# STRWHL-S05-V00-Screen.net
KiCad netlist of a schematic drawn in Altium Designer
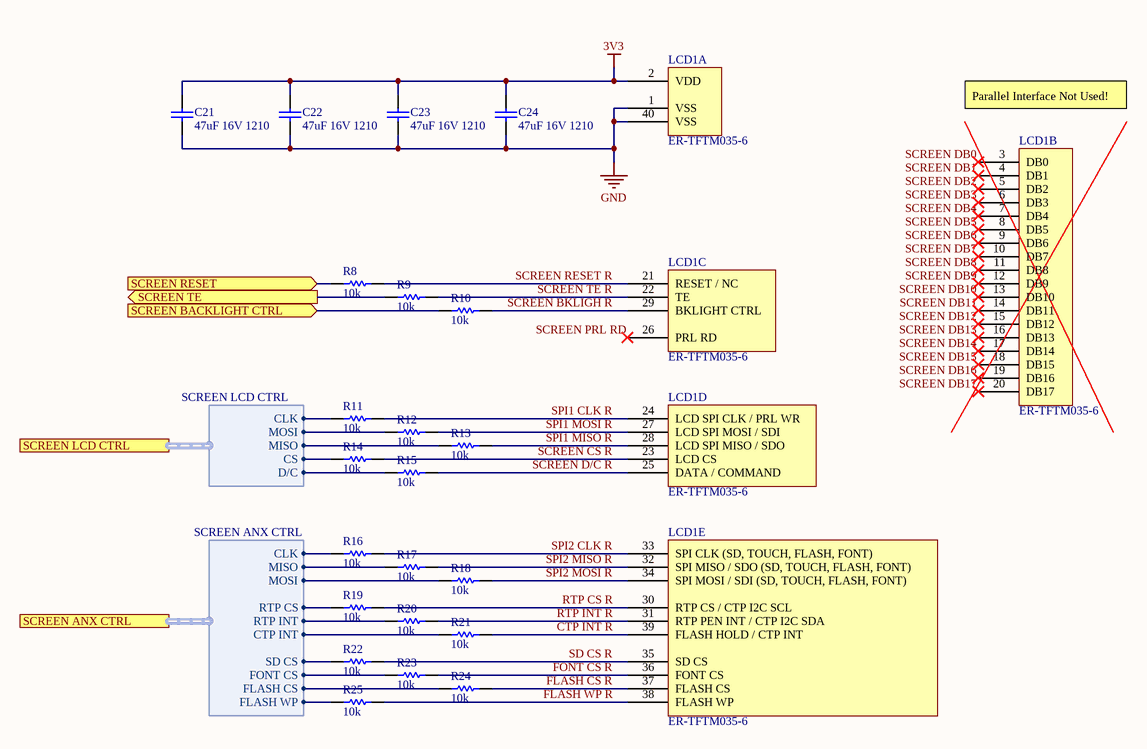
[diagram p0: STRWHL-S05-V00-Screen.SchDoc]

(export (version "E")
  (design (tool "Eeschema 10.0.6"))
  (components
    (comp (ref "C21")
      (value "47uF 16V 1210")
      (footprint "Cap_Ceramic_1210")
      (description "Capacitor, Ceramic, SMD, 47uF, 16V, 5%, X7R, 1210")
      (libsource (lib "StandardCapacitors") (part "47uF 16V 10% X7R 1210"))
    )
    (comp (ref "C22")
      (value "47uF 16V 1210")
      (footprint "Cap_Ceramic_1210")
      (description "Capacitor, Ceramic, SMD, 47uF, 16V, 5%, X7R, 1210")
      (libsource (lib "StandardCapacitors") (part "47uF 16V 10% X7R 1210"))
    )
    (comp (ref "C23")
      (value "47uF 16V 1210")
      (footprint "Cap_Ceramic_1210")
      (description "Capacitor, Ceramic, SMD, 47uF, 16V, 5%, X7R, 1210")
      (libsource (lib "StandardCapacitors") (part "47uF 16V 10% X7R 1210"))
    )
    (comp (ref "C24")
      (value "47uF 16V 1210")
      (footprint "Cap_Ceramic_1210")
      (description "Capacitor, Ceramic, SMD, 47uF, 16V, 5%, X7R, 1210")
      (libsource (lib "StandardCapacitors") (part "47uF 16V 10% X7R 1210"))
    )
    (comp (ref "LCD1")
      (value "ER-TFTM035-6")
      (footprint "ER-TFTM035-6")
      (description "LCD 3.5\" 320x480 TFT Display Module, OPTL Touch Screen w/Breakout Board")
      (libsource (lib "QUTMS_ScreenLibrary") (part "ER-TFTM035-6"))
    )
    (comp (ref "R8")
      (value "10k")
      (footprint "Res_ThinFilm_0603")
      (description "Resistor, SMD, 10k, 0.1W, 5%, 0603")
      (libsource (lib "StandardResistors") (part "10k 5% 0603"))
    )
    (comp (ref "R9")
      (value "10k")
      (footprint "Res_ThinFilm_0603")
      (description "Resistor, SMD, 10k, 0.1W, 5%, 0603")
      (libsource (lib "StandardResistors") (part "10k 5% 0603"))
    )
    (comp (ref "R10")
      (value "10k")
      (footprint "Res_ThinFilm_0603")
      (description "Resistor, SMD, 10k, 0.1W, 5%, 0603")
      (libsource (lib "StandardResistors") (part "10k 5% 0603"))
    )
    (comp (ref "R11")
      (value "10k")
      (footprint "Res_ThinFilm_0603")
      (description "Resistor, SMD, 10k, 0.1W, 5%, 0603")
      (libsource (lib "StandardResistors") (part "10k 5% 0603"))
    )
    (comp (ref "R12")
      (value "10k")
      (footprint "Res_ThinFilm_0603")
      (description "Resistor, SMD, 10k, 0.1W, 5%, 0603")
      (libsource (lib "StandardResistors") (part "10k 5% 0603"))
    )
    (comp (ref "R13")
      (value "10k")
      (footprint "Res_ThinFilm_0603")
      (description "Resistor, SMD, 10k, 0.1W, 5%, 0603")
      (libsource (lib "StandardResistors") (part "10k 5% 0603"))
    )
    (comp (ref "R14")
      (value "10k")
      (footprint "Res_ThinFilm_0603")
      (description "Resistor, SMD, 10k, 0.1W, 5%, 0603")
      (libsource (lib "StandardResistors") (part "10k 5% 0603"))
    )
    (comp (ref "R15")
      (value "10k")
      (footprint "Res_ThinFilm_0603")
      (description "Resistor, SMD, 10k, 0.1W, 5%, 0603")
      (libsource (lib "StandardResistors") (part "10k 5% 0603"))
    )
    (comp (ref "R16")
      (value "10k")
      (footprint "Res_ThinFilm_0603")
      (description "Resistor, SMD, 10k, 0.1W, 5%, 0603")
      (libsource (lib "StandardResistors") (part "10k 5% 0603"))
    )
    (comp (ref "R17")
      (value "10k")
      (footprint "Res_ThinFilm_0603")
      (description "Resistor, SMD, 10k, 0.1W, 5%, 0603")
      (libsource (lib "StandardResistors") (part "10k 5% 0603"))
    )
    (comp (ref "R18")
      (value "10k")
      (footprint "Res_ThinFilm_0603")
      (description "Resistor, SMD, 10k, 0.1W, 5%, 0603")
      (libsource (lib "StandardResistors") (part "10k 5% 0603"))
    )
    (comp (ref "R19")
      (value "10k")
      (footprint "Res_ThinFilm_0603")
      (description "Resistor, SMD, 10k, 0.1W, 5%, 0603")
      (libsource (lib "StandardResistors") (part "10k 5% 0603"))
    )
    (comp (ref "R20")
      (value "10k")
      (footprint "Res_ThinFilm_0603")
      (description "Resistor, SMD, 10k, 0.1W, 5%, 0603")
      (libsource (lib "StandardResistors") (part "10k 5% 0603"))
    )
    (comp (ref "R21")
      (value "10k")
      (footprint "Res_ThinFilm_0603")
      (description "Resistor, SMD, 10k, 0.1W, 5%, 0603")
      (libsource (lib "StandardResistors") (part "10k 5% 0603"))
    )
    (comp (ref "R22")
      (value "10k")
      (footprint "Res_ThinFilm_0603")
      (description "Resistor, SMD, 10k, 0.1W, 5%, 0603")
      (libsource (lib "StandardResistors") (part "10k 5% 0603"))
    )
    (comp (ref "R23")
      (value "10k")
      (footprint "Res_ThinFilm_0603")
      (description "Resistor, SMD, 10k, 0.1W, 5%, 0603")
      (libsource (lib "StandardResistors") (part "10k 5% 0603"))
    )
    (comp (ref "R24")
      (value "10k")
      (footprint "Res_ThinFilm_0603")
      (description "Resistor, SMD, 10k, 0.1W, 5%, 0603")
      (libsource (lib "StandardResistors") (part "10k 5% 0603"))
    )
    (comp (ref "R25")
      (value "10k")
      (footprint "Res_ThinFilm_0603")
      (description "Resistor, SMD, 10k, 0.1W, 5%, 0603")
      (libsource (lib "StandardResistors") (part "10k 5% 0603"))
    )
  )
  (nets
    (net (code "5") (name "/CS") (class "Default")
      (node (ref "R14") (pin "2") (pinfunction "2_2") (pintype "passive"))
    )
    (net (code "6") (name "/CTP INT") (class "Default")
      (node (ref "R21") (pin "2") (pinfunction "2_2") (pintype "passive"))
    )
    (net (code "7") (name "/CTP INT R") (class "Default")
      (node (ref "LCD1") (pin "39") (pinfunction "FLASH_HOLD_/_CTP_INT_39") (pintype "passive"))
      (node (ref "R21") (pin "1") (pinfunction "1_1") (pintype "passive"))
    )
    (net (code "8") (name "/D{slash}C") (class "Default")
      (node (ref "R15") (pin "2") (pinfunction "2_2") (pintype "passive"))
    )
    (net (code "9") (name "/FLASH CS") (class "Default")
      (node (ref "R24") (pin "2") (pinfunction "2_2") (pintype "passive"))
    )
    (net (code "10") (name "/FLASH CS R") (class "Default")
      (node (ref "LCD1") (pin "37") (pinfunction "FLASH_CS_37") (pintype "passive"))
      (node (ref "R24") (pin "1") (pinfunction "1_1") (pintype "passive"))
    )
    (net (code "11") (name "/FLASH WP") (class "Default")
      (node (ref "R25") (pin "2") (pinfunction "2_2") (pintype "passive"))
    )
    (net (code "12") (name "/FLASH WP R") (class "Default")
      (node (ref "LCD1") (pin "38") (pinfunction "FLASH_WP_38") (pintype "passive"))
      (node (ref "R25") (pin "1") (pinfunction "1_1") (pintype "passive"))
    )
    (net (code "13") (name "/FONT CS") (class "Default")
      (node (ref "R23") (pin "2") (pinfunction "2_2") (pintype "passive"))
    )
    (net (code "14") (name "/FONT CS R") (class "Default")
      (node (ref "LCD1") (pin "36") (pinfunction "FONT_CS_36") (pintype "passive"))
      (node (ref "R23") (pin "1") (pinfunction "1_1") (pintype "passive"))
    )
    (net (code "15") (name "/RTP CS") (class "Default")
      (node (ref "R19") (pin "2") (pinfunction "2_2") (pintype "passive"))
    )
    (net (code "16") (name "/RTP CS R") (class "Default")
      (node (ref "LCD1") (pin "30") (pinfunction "RTP_CS_/_CTP_I2C_SCL_30") (pintype "passive"))
      (node (ref "R19") (pin "1") (pinfunction "1_1") (pintype "passive"))
    )
    (net (code "17") (name "/RTP INT") (class "Default")
      (node (ref "R20") (pin "2") (pinfunction "2_2") (pintype "passive"))
    )
    (net (code "18") (name "/RTP INT R") (class "Default")
      (node (ref "LCD1") (pin "31") (pinfunction "RTP_PEN_INT_/_CTP_I2C_SDA_31") (pintype "passive"))
      (node (ref "R20") (pin "1") (pinfunction "1_1") (pintype "passive"))
    )
    (net (code "19") (name "/SCREEN BACKLIGHT CTRL") (class "Default")
      (node (ref "R10") (pin "2") (pinfunction "2_2") (pintype "passive"))
    )
    (net (code "20") (name "/SCREEN BKLIGH R") (class "Default")
      (node (ref "LCD1") (pin "29") (pinfunction "BKLIGHT_CTRL_29") (pintype "passive"))
      (node (ref "R10") (pin "1") (pinfunction "1_1") (pintype "passive"))
    )
    (net (code "21") (name "/SCREEN CS R") (class "Default")
      (node (ref "LCD1") (pin "23") (pinfunction "LCD_CS_23") (pintype "passive"))
      (node (ref "R14") (pin "1") (pinfunction "1_1") (pintype "passive"))
    )
    (net (code "22") (name "/SCREEN DB0") (class "Default")
      (node (ref "LCD1") (pin "3") (pinfunction "DB0_3") (pintype "passive+no_connect"))
    )
    (net (code "23") (name "/SCREEN DB1") (class "Default")
      (node (ref "LCD1") (pin "4") (pinfunction "DB1_4") (pintype "passive+no_connect"))
    )
    (net (code "24") (name "/SCREEN DB2") (class "Default")
      (node (ref "LCD1") (pin "5") (pinfunction "DB2_5") (pintype "passive+no_connect"))
    )
    (net (code "25") (name "/SCREEN DB3") (class "Default")
      (node (ref "LCD1") (pin "6") (pinfunction "DB3_6") (pintype "passive+no_connect"))
    )
    (net (code "26") (name "/SCREEN DB4") (class "Default")
      (node (ref "LCD1") (pin "7") (pinfunction "DB4_7") (pintype "passive+no_connect"))
    )
    (net (code "27") (name "/SCREEN DB5") (class "Default")
      (node (ref "LCD1") (pin "8") (pinfunction "DB5_8") (pintype "passive+no_connect"))
    )
    (net (code "28") (name "/SCREEN DB6") (class "Default")
      (node (ref "LCD1") (pin "9") (pinfunction "DB6_9") (pintype "passive+no_connect"))
    )
    (net (code "29") (name "/SCREEN DB7") (class "Default")
      (node (ref "LCD1") (pin "10") (pinfunction "DB7_10") (pintype "passive+no_connect"))
    )
    (net (code "30") (name "/SCREEN DB8") (class "Default")
      (node (ref "LCD1") (pin "11") (pinfunction "DB8_11") (pintype "passive+no_connect"))
    )
    (net (code "31") (name "/SCREEN DB9") (class "Default")
      (node (ref "LCD1") (pin "12") (pinfunction "DB9_12") (pintype "passive+no_connect"))
    )
    (net (code "32") (name "/SCREEN DB10") (class "Default")
      (node (ref "LCD1") (pin "13") (pinfunction "DB10_13") (pintype "passive+no_connect"))
    )
    (net (code "33") (name "/SCREEN DB11") (class "Default")
      (node (ref "LCD1") (pin "14") (pinfunction "DB11_14") (pintype "passive+no_connect"))
    )
    (net (code "34") (name "/SCREEN DB12") (class "Default")
      (node (ref "LCD1") (pin "15") (pinfunction "DB12_15") (pintype "passive+no_connect"))
    )
    (net (code "35") (name "/SCREEN DB13") (class "Default")
      (node (ref "LCD1") (pin "16") (pinfunction "DB13_16") (pintype "passive+no_connect"))
    )
    (net (code "36") (name "/SCREEN DB14") (class "Default")
      (node (ref "LCD1") (pin "17") (pinfunction "DB14_17") (pintype "passive+no_connect"))
    )
    (net (code "37") (name "/SCREEN DB15") (class "Default")
      (node (ref "LCD1") (pin "18") (pinfunction "DB15_18") (pintype "passive+no_connect"))
    )
    (net (code "38") (name "/SCREEN DB16") (class "Default")
      (node (ref "LCD1") (pin "19") (pinfunction "DB16_19") (pintype "passive+no_connect"))
    )
    (net (code "39") (name "/SCREEN DB17") (class "Default")
      (node (ref "LCD1") (pin "20") (pinfunction "DB17_20") (pintype "passive+no_connect"))
    )
    (net (code "40") (name "/SCREEN D{slash}C R") (class "Default")
      (node (ref "LCD1") (pin "25") (pinfunction "DATA_/_COMMAND_25") (pintype "passive"))
      (node (ref "R15") (pin "1") (pinfunction "1_1") (pintype "passive"))
    )
    (net (code "41") (name "/SCREEN PRL RD") (class "Default")
      (node (ref "LCD1") (pin "26") (pinfunction "PRL_RD_26") (pintype "passive+no_connect"))
    )
    (net (code "42") (name "/SCREEN RESET") (class "Default")
      (node (ref "R8") (pin "2") (pinfunction "2_2") (pintype "passive"))
    )
    (net (code "43") (name "/SCREEN RESET R") (class "Default")
      (node (ref "LCD1") (pin "21") (pinfunction "RESET_/_NC_21") (pintype "passive"))
      (node (ref "R8") (pin "1") (pinfunction "1_1") (pintype "passive"))
    )
    (net (code "44") (name "/SCREEN TE") (class "Default")
      (node (ref "R9") (pin "2") (pinfunction "2_2") (pintype "passive"))
    )
    (net (code "45") (name "/SCREEN TE R") (class "Default")
      (node (ref "LCD1") (pin "22") (pinfunction "TE_22") (pintype "passive"))
      (node (ref "R9") (pin "1") (pinfunction "1_1") (pintype "passive"))
    )
    (net (code "46") (name "/SD CS") (class "Default")
      (node (ref "R22") (pin "2") (pinfunction "2_2") (pintype "passive"))
    )
    (net (code "47") (name "/SD CS R") (class "Default")
      (node (ref "LCD1") (pin "35") (pinfunction "SD_CS_35") (pintype "passive"))
      (node (ref "R22") (pin "1") (pinfunction "1_1") (pintype "passive"))
    )
    (net (code "48") (name "/SPI1 CLK R") (class "Default")
      (node (ref "LCD1") (pin "24") (pinfunction "LCD_SPI_CLK_/_PRL_WR_24") (pintype "passive"))
      (node (ref "R11") (pin "1") (pinfunction "1_1") (pintype "passive"))
    )
    (net (code "49") (name "/SPI1 MISO R") (class "Default")
      (node (ref "LCD1") (pin "28") (pinfunction "LCD_SPI_MISO_/_SDO_28") (pintype "passive"))
      (node (ref "R13") (pin "1") (pinfunction "1_1") (pintype "passive"))
    )
    (net (code "50") (name "/SPI1 MOSI R") (class "Default")
      (node (ref "LCD1") (pin "27") (pinfunction "LCD_SPI_MOSI_/_SDI_27") (pintype "passive"))
      (node (ref "R12") (pin "1") (pinfunction "1_1") (pintype "passive"))
    )
    (net (code "51") (name "/SPI2 CLK R") (class "Default")
      (node (ref "LCD1") (pin "33") (pinfunction "SPI_CLK_(SD,_TOUCH,_FLASH,_FONT)_33") (pintype "passive"))
      (node (ref "R16") (pin "1") (pinfunction "1_1") (pintype "passive"))
    )
    (net (code "52") (name "/SPI2 MISO R") (class "Default")
      (node (ref "LCD1") (pin "32") (pinfunction "SPI_MISO_/_SDO_(SD,_TOUCH,_FLASH,_FONT)_32") (pintype "passive"))
      (node (ref "R17") (pin "1") (pinfunction "1_1") (pintype "passive"))
    )
    (net (code "53") (name "/SPI2 MOSI R") (class "Default")
      (node (ref "LCD1") (pin "34") (pinfunction "SPI_MOSI_/_SDI_(SD,_TOUCH,_FLASH,_FONT)_34") (pintype "passive"))
      (node (ref "R18") (pin "1") (pinfunction "1_1") (pintype "passive"))
    )
    (net (code "56") (name "3V3") (class "Default")
      (node (ref "C21") (pin "2") (pinfunction "2_2") (pintype "passive"))
      (node (ref "C22") (pin "2") (pinfunction "2_2") (pintype "passive"))
      (node (ref "C23") (pin "2") (pinfunction "2_2") (pintype "passive"))
      (node (ref "C24") (pin "2") (pinfunction "2_2") (pintype "passive"))
      (node (ref "LCD1") (pin "2") (pinfunction "VDD_2") (pintype "passive"))
    )
    (net (code "57") (name "GND") (class "Default")
      (node (ref "C21") (pin "1") (pinfunction "1_1") (pintype "passive"))
      (node (ref "C22") (pin "1") (pinfunction "1_1") (pintype "passive"))
      (node (ref "C23") (pin "1") (pinfunction "1_1") (pintype "passive"))
      (node (ref "C24") (pin "1") (pinfunction "1_1") (pintype "passive"))
      (node (ref "LCD1") (pin "1") (pinfunction "VSS_1") (pintype "passive"))
      (node (ref "LCD1") (pin "40") (pinfunction "VSS_40") (pintype "passive"))
    )
    (net (code "58") (name "unconnected-(R11-Pad2)") (class "Default")
      (node (ref "R11") (pin "2") (pinfunction "2_2") (pintype "passive"))
    )
    (net (code "59") (name "unconnected-(R12-Pad2)") (class "Default")
      (node (ref "R12") (pin "2") (pinfunction "2_2") (pintype "passive"))
    )
    (net (code "60") (name "unconnected-(R13-Pad2)") (class "Default")
      (node (ref "R13") (pin "2") (pinfunction "2_2") (pintype "passive"))
    )
    (net (code "61") (name "unconnected-(R16-Pad2)") (class "Default")
      (node (ref "R16") (pin "2") (pinfunction "2_2") (pintype "passive"))
    )
    (net (code "62") (name "unconnected-(R17-Pad2)") (class "Default")
      (node (ref "R17") (pin "2") (pinfunction "2_2") (pintype "passive"))
    )
    (net (code "63") (name "unconnected-(R18-Pad2)") (class "Default")
      (node (ref "R18") (pin "2") (pinfunction "2_2") (pintype "passive"))
    )
  )
)
